# epd.net
KiCad netlist of a schematic drawn in Altium Designer
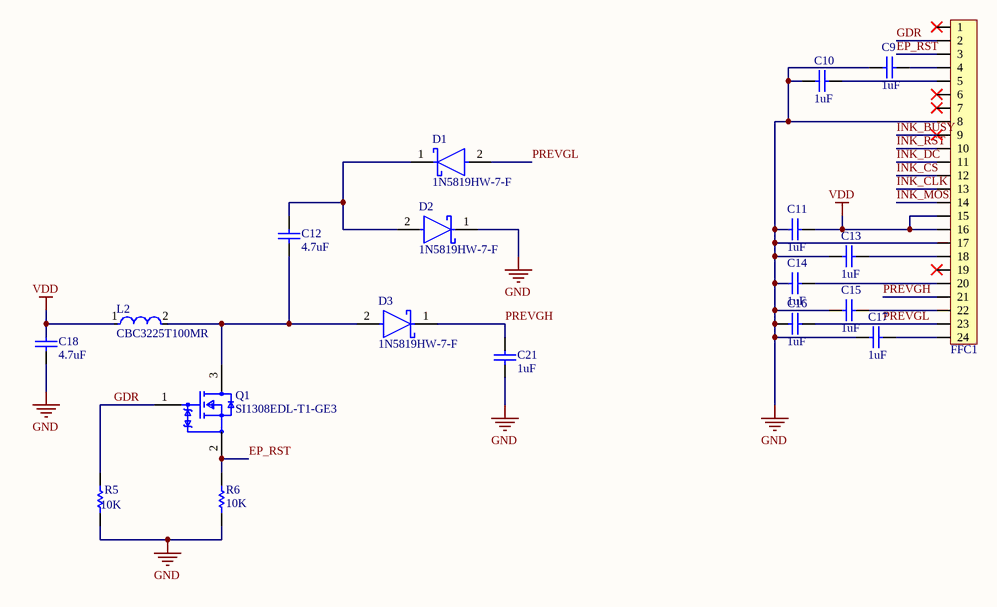
[diagram p0: epd.SchDoc]

(export (version "E")
  (design (tool "Eeschema 10.0.6"))
  (components
    (comp (ref "C9")
      (value "1uF")
      (footprint "C0402")
      (description "Capacitor,1uF,6V3,X5R,10%,0402")
      (fields
        (field (name "INTERNAL_PART_NUMBER") "MCD-00095")
        (field (name "MANUFACTURER_PART_NUMBER") "GRM155R61E105KA12")
        (field (name "PROVIDED_BY") "SUBCO")
      )
      (libsource (lib "MB1272") (part "MCD-00095"))
    )
    (comp (ref "C10")
      (value "1uF")
      (footprint "C0402")
      (description "Capacitor,1uF,6V3,X5R,10%,0402")
      (fields
        (field (name "INTERNAL_PART_NUMBER") "MCD-00095")
        (field (name "MANUFACTURER_PART_NUMBER") "GRM155R61E105KA12")
        (field (name "PROVIDED_BY") "SUBCO")
      )
      (libsource (lib "MB1272") (part "MCD-00095"))
    )
    (comp (ref "C11")
      (value "1uF")
      (footprint "C0402")
      (description "Capacitor,1uF,6V3,X5R,10%,0402")
      (fields
        (field (name "INTERNAL_PART_NUMBER") "MCD-00095")
        (field (name "MANUFACTURER_PART_NUMBER") "GRM155R61E105KA12")
        (field (name "PROVIDED_BY") "SUBCO")
      )
      (libsource (lib "MB1272") (part "MCD-00095"))
    )
    (comp (ref "C12")
      (value "4.7uF")
      (footprint "C0402")
      (description "Capacitor, MLCC, 4.7uF, 6V3, X5R, 20%, 0402, T=0,5mm")
      (fields
        (field (name "INTERNAL_PART_NUMBER") "MCD-01356")
        (field (name "MANUFACTURER_PART_NUMBER") "GRM155R60J475ME47")
        (field (name "PROVIDED_BY") "SUBCO")
      )
      (libsource (lib "MB1272") (part "MCD-01356"))
    )
    (comp (ref "C13")
      (value "1uF")
      (footprint "C0402")
      (description "Capacitor,1uF,6V3,X5R,10%,0402")
      (fields
        (field (name "INTERNAL_PART_NUMBER") "MCD-00095")
        (field (name "MANUFACTURER_PART_NUMBER") "GRM155R61E105KA12")
        (field (name "PROVIDED_BY") "SUBCO")
      )
      (libsource (lib "MB1272") (part "MCD-00095"))
    )
    (comp (ref "C14")
      (value "1uF")
      (footprint "C0402")
      (description "Capacitor,1uF,6V3,X5R,10%,0402")
      (fields
        (field (name "INTERNAL_PART_NUMBER") "MCD-00095")
        (field (name "MANUFACTURER_PART_NUMBER") "GRM155R61E105KA12")
        (field (name "PROVIDED_BY") "SUBCO")
      )
      (libsource (lib "MB1272") (part "MCD-00095"))
    )
    (comp (ref "C15")
      (value "1uF")
      (footprint "C0402")
      (description "Capacitor,1uF,6V3,X5R,10%,0402")
      (fields
        (field (name "INTERNAL_PART_NUMBER") "MCD-00095")
        (field (name "MANUFACTURER_PART_NUMBER") "GRM155R61E105KA12")
        (field (name "PROVIDED_BY") "SUBCO")
      )
      (libsource (lib "MB1272") (part "MCD-00095"))
    )
    (comp (ref "C16")
      (value "1uF")
      (footprint "C0402")
      (description "Capacitor,1uF,6V3,X5R,10%,0402")
      (fields
        (field (name "INTERNAL_PART_NUMBER") "MCD-00095")
        (field (name "MANUFACTURER_PART_NUMBER") "GRM155R61E105KA12")
        (field (name "PROVIDED_BY") "SUBCO")
      )
      (libsource (lib "MB1272") (part "MCD-00095"))
    )
    (comp (ref "C17")
      (value "1uF")
      (footprint "C0402")
      (description "Capacitor,1uF,6V3,X5R,10%,0402")
      (fields
        (field (name "INTERNAL_PART_NUMBER") "MCD-00095")
        (field (name "MANUFACTURER_PART_NUMBER") "GRM155R61E105KA12")
        (field (name "PROVIDED_BY") "SUBCO")
      )
      (libsource (lib "MB1272") (part "MCD-00095"))
    )
    (comp (ref "C18")
      (value "4.7uF")
      (footprint "C0402")
      (description "Capacitor, MLCC, 4.7uF, 6V3, X5R, 20%, 0402, T=0,5mm")
      (fields
        (field (name "INTERNAL_PART_NUMBER") "MCD-01356")
        (field (name "MANUFACTURER_PART_NUMBER") "GRM155R60J475ME47")
        (field (name "PROVIDED_BY") "SUBCO")
      )
      (libsource (lib "MB1272") (part "MCD-01356"))
    )
    (comp (ref "C21")
      (value "1uF")
      (footprint "C0402")
      (description "Capacitor,1uF,6V3,X5R,10%,0402")
      (fields
        (field (name "INTERNAL_PART_NUMBER") "MCD-00095")
        (field (name "MANUFACTURER_PART_NUMBER") "GRM155R61E105KA12")
        (field (name "PROVIDED_BY") "SUBCO")
      )
      (libsource (lib "MB1272") (part "MCD-00095"))
    )
    (comp (ref "D1")
      (value "1N5819HW-7-F")
      (footprint "FP-SOD123-IPC_A")
      (description "DIODE SCHOTTKY 40V 1A SOD123")
      (libsource (lib "Altium Content Vault") (part "1d6ec82d83fb6aee721767c19dac4b9"))
    )
    (comp (ref "D2")
      (value "1N5819HW-7-F")
      (footprint "FP-SOD123-IPC_A")
      (description "DIODE SCHOTTKY 40V 1A SOD123")
      (libsource (lib "Altium Content Vault") (part "1d6ec82d83fb6aee721767c19dac4b9"))
    )
    (comp (ref "D3")
      (value "1N5819HW-7-F")
      (footprint "FP-SOD123-IPC_A")
      (description "DIODE SCHOTTKY 40V 1A SOD123")
      (libsource (lib "Altium Content Vault") (part "1d6ec82d83fb6aee721767c19dac4b9"))
    )
    (comp (ref "FFC1")
      (value "FFC_0.5_24")
      (footprint "FFC_0.5_24_INK")
      (description "FFC")
      (libsource (lib "MyPcbLib") (part "FFC_0.5_24_INK"))
    )
    (comp (ref "L2")
      (value "CBC3225T100MR")
      (footprint "FP-CB3225-IPC_A")
      (description "SMD Inductors 10uH ±20% 0.9A 0.1729Ω 1210")
      (fields (field (name "TOLERANCE") "20%"))
      (libsource (lib "Altium Content Vault") (part "725321dda6339637d4d059423bc1c3c"))
    )
    (comp (ref "Q1")
      (value "SI1308EDL-T1-GE3")
      (footprint "FP-5549-MFG")
      (description "MOSFET N-CH 30V 1.4A SC-70-3")
      (libsource (lib "Altium Content Vault") (part "e96677422f20f20903245877d22b385"))
    )
    (comp (ref "R5")
      (value "10K")
      (footprint "R0402")
      (description "Resistor,10K,0402,1%,1/16W")
      (fields
        (field (name "INTERNAL_PART_NUMBER") "MCD-00053")
        (field (name "MANUFACTURER_PART_NUMBER") "RC0402FR-0710KL")
        (field (name "PROVIDED_BY") "SUBCO")
      )
      (libsource (lib "MB1272") (part "MCD-00053"))
    )
    (comp (ref "R6")
      (value "10K")
      (footprint "R0402")
      (description "Resistor,10K,0402,1%,1/16W")
      (fields
        (field (name "INTERNAL_PART_NUMBER") "MCD-00053")
        (field (name "MANUFACTURER_PART_NUMBER") "RC0402FR-0710KL")
        (field (name "PROVIDED_BY") "SUBCO")
      )
      (libsource (lib "MB1272") (part "MCD-00053"))
    )
  )
  (nets
    (net (code "1") (name "/EP_RST") (class "Default")
      (node (ref "FFC1") (pin "3") (pinfunction "3_3") (pintype "passive"))
      (node (ref "Q1") (pin "2") (pinfunction "S_2") (pintype "passive"))
      (node (ref "R6") (pin "2") (pinfunction "2_2") (pintype "passive"))
    )
    (net (code "2") (name "/GDR") (class "Default")
      (node (ref "FFC1") (pin "2") (pinfunction "2_2") (pintype "passive"))
      (node (ref "Q1") (pin "1") (pinfunction "G_1") (pintype "passive"))
      (node (ref "R5") (pin "2") (pinfunction "2_2") (pintype "passive"))
    )
    (net (code "3") (name "/INK_BUSY") (class "Default")
      (node (ref "FFC1") (pin "9") (pinfunction "9_9") (pintype "passive+no_connect"))
    )
    (net (code "4") (name "/INK_CLK") (class "Default")
      (node (ref "FFC1") (pin "13") (pinfunction "13_13") (pintype "passive"))
    )
    (net (code "5") (name "/INK_CS") (class "Default")
      (node (ref "FFC1") (pin "12") (pinfunction "12_12") (pintype "passive"))
    )
    (net (code "6") (name "/INK_DC") (class "Default")
      (node (ref "FFC1") (pin "11") (pinfunction "11_11") (pintype "passive"))
    )
    (net (code "7") (name "/INK_MOSI") (class "Default")
      (node (ref "FFC1") (pin "14") (pinfunction "14_14") (pintype "passive"))
    )
    (net (code "8") (name "/INK_RST") (class "Default")
      (node (ref "FFC1") (pin "10") (pinfunction "10_10") (pintype "passive"))
    )
    (net (code "9") (name "/PREVGH") (class "Default")
      (node (ref "C21") (pin "2") (pinfunction "2_2") (pintype "passive"))
      (node (ref "D3") (pin "1") (pinfunction "C_1") (pintype "passive"))
      (node (ref "FFC1") (pin "21") (pinfunction "21_21") (pintype "passive"))
    )
    (net (code "10") (name "/PREVGL") (class "Default")
      (node (ref "C16") (pin "2") (pinfunction "2_2") (pintype "passive"))
      (node (ref "D1") (pin "2") (pinfunction "A_2") (pintype "passive"))
      (node (ref "FFC1") (pin "23") (pinfunction "23_23") (pintype "passive"))
    )
    (net (code "11") (name "GND") (class "Default")
      (node (ref "C10") (pin "1") (pinfunction "1_1") (pintype "passive"))
      (node (ref "C11") (pin "1") (pinfunction "1_1") (pintype "passive"))
      (node (ref "C13") (pin "1") (pinfunction "1_1") (pintype "passive"))
      (node (ref "C14") (pin "1") (pinfunction "1_1") (pintype "passive"))
      (node (ref "C15") (pin "1") (pinfunction "1_1") (pintype "passive"))
      (node (ref "C16") (pin "1") (pinfunction "1_1") (pintype "passive"))
      (node (ref "C17") (pin "1") (pinfunction "1_1") (pintype "passive"))
      (node (ref "C18") (pin "1") (pinfunction "1_1") (pintype "passive"))
      (node (ref "C21") (pin "1") (pinfunction "1_1") (pintype "passive"))
      (node (ref "C9") (pin "1") (pinfunction "1_1") (pintype "passive"))
      (node (ref "D2") (pin "1") (pinfunction "C_1") (pintype "passive"))
      (node (ref "FFC1") (pin "17") (pinfunction "17_17") (pintype "passive"))
      (node (ref "FFC1") (pin "8") (pinfunction "8_8") (pintype "passive"))
      (node (ref "R5") (pin "1") (pinfunction "1_1") (pintype "passive"))
      (node (ref "R6") (pin "1") (pinfunction "1_1") (pintype "passive"))
    )
    (net (code "12") (name "Net-(C9-Pad2)") (class "Default")
      (node (ref "C9") (pin "2") (pinfunction "2_2") (pintype "passive"))
      (node (ref "FFC1") (pin "4") (pinfunction "4_4") (pintype "passive"))
    )
    (net (code "13") (name "Net-(C10-Pad2)") (class "Default")
      (node (ref "C10") (pin "2") (pinfunction "2_2") (pintype "passive"))
      (node (ref "FFC1") (pin "5") (pinfunction "5_5") (pintype "passive"))
    )
    (net (code "14") (name "Net-(C13-Pad2)") (class "Default")
      (node (ref "C13") (pin "2") (pinfunction "2_2") (pintype "passive"))
      (node (ref "FFC1") (pin "18") (pinfunction "18_18") (pintype "passive"))
    )
    (net (code "15") (name "Net-(C14-Pad2)") (class "Default")
      (node (ref "C14") (pin "2") (pinfunction "2_2") (pintype "passive"))
      (node (ref "FFC1") (pin "20") (pinfunction "20_20") (pintype "passive"))
    )
    (net (code "16") (name "Net-(C15-Pad2)") (class "Default")
      (node (ref "C15") (pin "2") (pinfunction "2_2") (pintype "passive"))
      (node (ref "FFC1") (pin "22") (pinfunction "22_22") (pintype "passive"))
    )
    (net (code "17") (name "Net-(C17-Pad2)") (class "Default")
      (node (ref "C17") (pin "2") (pinfunction "2_2") (pintype "passive"))
      (node (ref "FFC1") (pin "24") (pinfunction "24_24") (pintype "passive"))
    )
    (net (code "18") (name "Net-(D1-C)") (class "Default")
      (node (ref "C12") (pin "2") (pinfunction "2_2") (pintype "passive"))
      (node (ref "D1") (pin "1") (pinfunction "C_1") (pintype "passive"))
      (node (ref "D2") (pin "2") (pinfunction "A_2") (pintype "passive"))
    )
    (net (code "19") (name "Net-(D3-A)") (class "Default")
      (node (ref "C12") (pin "1") (pinfunction "1_1") (pintype "passive"))
      (node (ref "D3") (pin "2") (pinfunction "A_2") (pintype "passive"))
      (node (ref "L2") (pin "2") (pinfunction "2_2") (pintype "passive"))
      (node (ref "Q1") (pin "3") (pinfunction "D_3") (pintype "passive"))
    )
    (net (code "20") (name "VDD") (class "Default")
      (node (ref "C11") (pin "2") (pinfunction "2_2") (pintype "passive"))
      (node (ref "C18") (pin "2") (pinfunction "2_2") (pintype "passive"))
      (node (ref "FFC1") (pin "15") (pinfunction "15_15") (pintype "passive"))
      (node (ref "FFC1") (pin "16") (pinfunction "16_16") (pintype "passive"))
      (node (ref "L2") (pin "1") (pinfunction "1_1") (pintype "passive"))
    )
    (net (code "21") (name "unconnected-(FFC1-Pad1)") (class "Default")
      (node (ref "FFC1") (pin "1") (pinfunction "1_1") (pintype "passive+no_connect"))
    )
    (net (code "22") (name "unconnected-(FFC1-Pad6)") (class "Default")
      (node (ref "FFC1") (pin "6") (pinfunction "6_6") (pintype "passive+no_connect"))
    )
    (net (code "23") (name "unconnected-(FFC1-Pad7)") (class "Default")
      (node (ref "FFC1") (pin "7") (pinfunction "7_7") (pintype "passive+no_connect"))
    )
    (net (code "24") (name "unconnected-(FFC1-Pad19)") (class "Default")
      (node (ref "FFC1") (pin "19") (pinfunction "19_19") (pintype "passive+no_connect"))
    )
  )
)
